# S1_Interface.net
KiCad netlist of a schematic drawn in Altium Designer
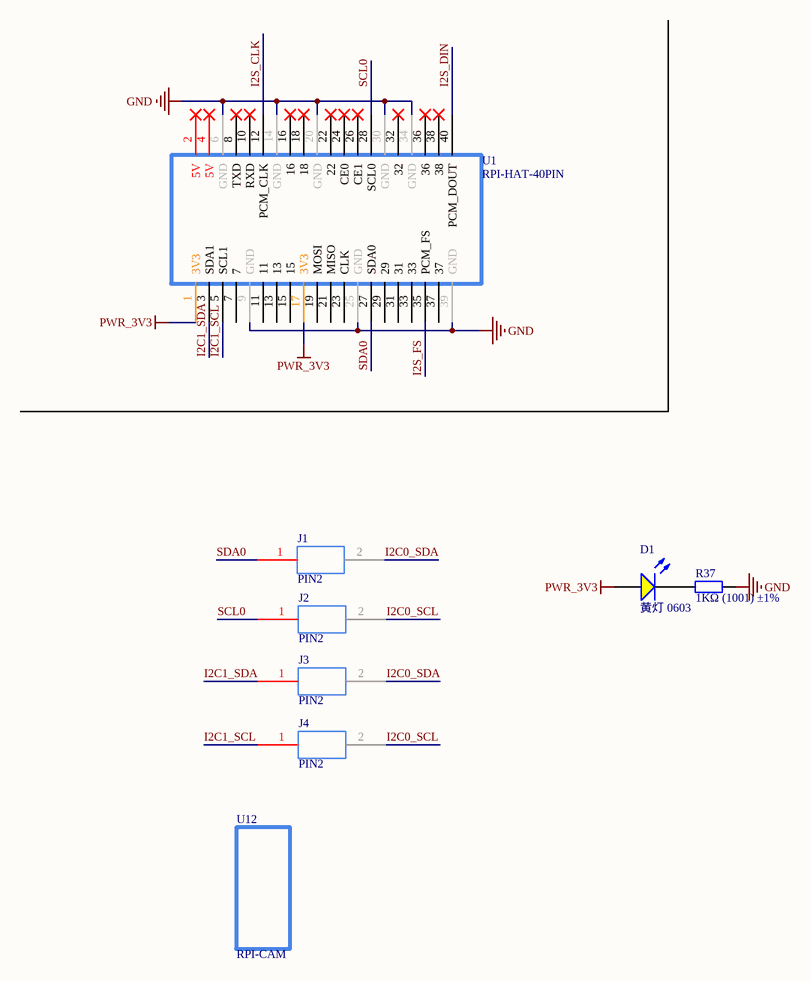
[diagram p0: S1_Interface.SchDoc]

(export (version "E")
  (design (tool "Eeschema 10.0.6"))
  (components
    (comp (ref "D1")
      (value "黄灯 0603")
      (footprint "0603_LED_S1")
      (description "发光二极管")
      (libsource (lib "Miscellaneous Devices LC") (part "0603 黄灯"))
    )
    (comp (ref "J1") (value "PIN2") (footprint "PIN2") (libsource (lib "Moon") (part "PIN2")))
    (comp (ref "J2") (value "PIN2") (footprint "PIN2") (libsource (lib "Moon") (part "PIN2")))
    (comp (ref "J3") (value "PIN2") (footprint "PIN2") (libsource (lib "Moon") (part "PIN2")))
    (comp (ref "J4") (value "PIN2") (footprint "PIN2") (libsource (lib "Moon") (part "PIN2")))
    (comp (ref "R37")
      (value "1KΩ (1001) ±1%")
      (footprint "0603_R")
      (description "贴片电阻")
      (libsource (lib "Miscellaneous Devices LC") (part "0603 1KΩ (1001) 1%"))
    )
    (comp (ref "U1")
      (value "RPI-HAT-40PIN")
      (footprint "RPI-HAT-40PIN")
      (libsource (lib "Sensor") (part "RPI-HAT-40PIN"))
    )
    (comp (ref "U12") (value "RPI-CAM") (footprint "RPI-CAM") (libsource (lib "Sensor") (part "RPI-CAM")))
  )
  (nets
    (net (code "1") (name "/I2C0_SCL") (class "Default")
      (node (ref "J2") (pin "2") (pinfunction "GND_2") (pintype "passive"))
      (node (ref "J4") (pin "2") (pinfunction "GND_2") (pintype "passive"))
    )
    (net (code "2") (name "/I2C0_SDA") (class "Default")
      (node (ref "J1") (pin "2") (pinfunction "GND_2") (pintype "passive"))
      (node (ref "J3") (pin "2") (pinfunction "GND_2") (pintype "passive"))
    )
    (net (code "3") (name "/I2C1_SCL") (class "Default")
      (node (ref "J4") (pin "1") (pinfunction "VCC_1") (pintype "passive"))
      (node (ref "U1") (pin "5") (pinfunction "SCL1_5") (pintype "passive"))
    )
    (net (code "4") (name "/I2C1_SDA") (class "Default")
      (node (ref "J3") (pin "1") (pinfunction "VCC_1") (pintype "passive"))
      (node (ref "U1") (pin "3") (pinfunction "SDA1_3") (pintype "passive"))
    )
    (net (code "5") (name "/I2S_CLK") (class "Default")
      (node (ref "U1") (pin "12") (pinfunction "PCM_CLK_12") (pintype "passive"))
    )
    (net (code "6") (name "/I2S_DIN") (class "Default")
      (node (ref "U1") (pin "40") (pinfunction "PCM_DOUT_40") (pintype "passive"))
    )
    (net (code "7") (name "/I2S_FS") (class "Default")
      (node (ref "U1") (pin "35") (pinfunction "PCM_FS_35") (pintype "passive"))
    )
    (net (code "8") (name "/SCL0") (class "Default")
      (node (ref "J2") (pin "1") (pinfunction "VCC_1") (pintype "passive"))
      (node (ref "U1") (pin "28") (pinfunction "SCL0_28") (pintype "passive"))
    )
    (net (code "9") (name "/SDA0") (class "Default")
      (node (ref "J1") (pin "1") (pinfunction "VCC_1") (pintype "passive"))
      (node (ref "U1") (pin "27") (pinfunction "SDA0_27") (pintype "passive"))
    )
    (net (code "10") (name "GND") (class "Default")
      (node (ref "R37") (pin "2") (pinfunction "2_2") (pintype "passive"))
      (node (ref "U1") (pin "14") (pinfunction "GND_14") (pintype "passive"))
      (node (ref "U1") (pin "20") (pinfunction "GND_20") (pintype "passive"))
      (node (ref "U1") (pin "25") (pinfunction "GND_25") (pintype "passive"))
      (node (ref "U1") (pin "30") (pinfunction "GND_30") (pintype "passive"))
      (node (ref "U1") (pin "34") (pinfunction "GND_34") (pintype "passive"))
      (node (ref "U1") (pin "39") (pinfunction "GND_39") (pintype "passive"))
      (node (ref "U1") (pin "6") (pinfunction "GND_6") (pintype "passive"))
      (node (ref "U1") (pin "9") (pinfunction "GND_9") (pintype "passive"))
    )
    (net (code "11") (name "Net-(D1-PadK)") (class "Default")
      (node (ref "D1") (pin "K") (pinfunction "K_K") (pintype "passive"))
      (node (ref "R37") (pin "1") (pinfunction "1_1") (pintype "passive"))
    )
    (net (code "12") (name "PWR_3V3") (class "Default")
      (node (ref "D1") (pin "A") (pinfunction "A_A") (pintype "passive"))
      (node (ref "U1") (pin "1") (pinfunction "3V3_1") (pintype "passive"))
      (node (ref "U1") (pin "17") (pinfunction "3V3_17") (pintype "passive"))
    )
    (net (code "13") (name "unconnected-(U1-5V-Pad2)") (class "Default")
      (node (ref "U1") (pin "2") (pinfunction "5V_2") (pintype "passive+no_connect"))
    )
    (net (code "14") (name "unconnected-(U1-5V-Pad4)") (class "Default")
      (node (ref "U1") (pin "4") (pinfunction "5V_4") (pintype "passive+no_connect"))
    )
    (net (code "15") (name "unconnected-(U1-CE0-Pad24)") (class "Default")
      (node (ref "U1") (pin "24") (pinfunction "CE0_24") (pintype "passive+no_connect"))
    )
    (net (code "16") (name "unconnected-(U1-CE1-Pad26)") (class "Default")
      (node (ref "U1") (pin "26") (pinfunction "CE1_26") (pintype "passive+no_connect"))
    )
    (net (code "17") (name "unconnected-(U1-CLK-Pad23)") (class "Default")
      (node (ref "U1") (pin "23") (pinfunction "CLK_23") (pintype "passive"))
    )
    (net (code "18") (name "unconnected-(U1-MISO-Pad21)") (class "Default")
      (node (ref "U1") (pin "21") (pinfunction "MISO_21") (pintype "passive"))
    )
    (net (code "19") (name "unconnected-(U1-MOSI-Pad19)") (class "Default")
      (node (ref "U1") (pin "19") (pinfunction "MOSI_19") (pintype "passive"))
    )
    (net (code "20") (name "unconnected-(U1-Pad7)") (class "Default")
      (node (ref "U1") (pin "7") (pinfunction "7_7") (pintype "passive"))
    )
    (net (code "21") (name "unconnected-(U1-Pad11)") (class "Default")
      (node (ref "U1") (pin "11") (pinfunction "11_11") (pintype "passive"))
    )
    (net (code "22") (name "unconnected-(U1-Pad13)") (class "Default")
      (node (ref "U1") (pin "13") (pinfunction "13_13") (pintype "passive"))
    )
    (net (code "23") (name "unconnected-(U1-Pad15)") (class "Default")
      (node (ref "U1") (pin "15") (pinfunction "15_15") (pintype "passive"))
    )
    (net (code "24") (name "unconnected-(U1-Pad16)") (class "Default")
      (node (ref "U1") (pin "16") (pinfunction "16_16") (pintype "passive+no_connect"))
    )
    (net (code "25") (name "unconnected-(U1-Pad18)") (class "Default")
      (node (ref "U1") (pin "18") (pinfunction "18_18") (pintype "passive+no_connect"))
    )
    (net (code "26") (name "unconnected-(U1-Pad22)") (class "Default")
      (node (ref "U1") (pin "22") (pinfunction "22_22") (pintype "passive+no_connect"))
    )
    (net (code "27") (name "unconnected-(U1-Pad29)") (class "Default")
      (node (ref "U1") (pin "29") (pinfunction "29_29") (pintype "passive"))
    )
    (net (code "28") (name "unconnected-(U1-Pad31)") (class "Default")
      (node (ref "U1") (pin "31") (pinfunction "31_31") (pintype "passive"))
    )
    (net (code "29") (name "unconnected-(U1-Pad32)") (class "Default")
      (node (ref "U1") (pin "32") (pinfunction "32_32") (pintype "passive+no_connect"))
    )
    (net (code "30") (name "unconnected-(U1-Pad33)") (class "Default")
      (node (ref "U1") (pin "33") (pinfunction "33_33") (pintype "passive"))
    )
    (net (code "31") (name "unconnected-(U1-Pad36)") (class "Default")
      (node (ref "U1") (pin "36") (pinfunction "36_36") (pintype "passive+no_connect"))
    )
    (net (code "32") (name "unconnected-(U1-Pad37)") (class "Default")
      (node (ref "U1") (pin "37") (pinfunction "37_37") (pintype "passive"))
    )
    (net (code "33") (name "unconnected-(U1-Pad38)") (class "Default")
      (node (ref "U1") (pin "38") (pinfunction "38_38") (pintype "passive+no_connect"))
    )
    (net (code "34") (name "unconnected-(U1-RXD-Pad10)") (class "Default")
      (node (ref "U1") (pin "10") (pinfunction "RXD_10") (pintype "passive+no_connect"))
    )
    (net (code "35") (name "unconnected-(U1-TXD-Pad8)") (class "Default")
      (node (ref "U1") (pin "8") (pinfunction "TXD_8") (pintype "passive+no_connect"))
    )
  )
)
